# Tesseract_Pro-Mini.net
KiCad netlist of a schematic drawn in EAGLE
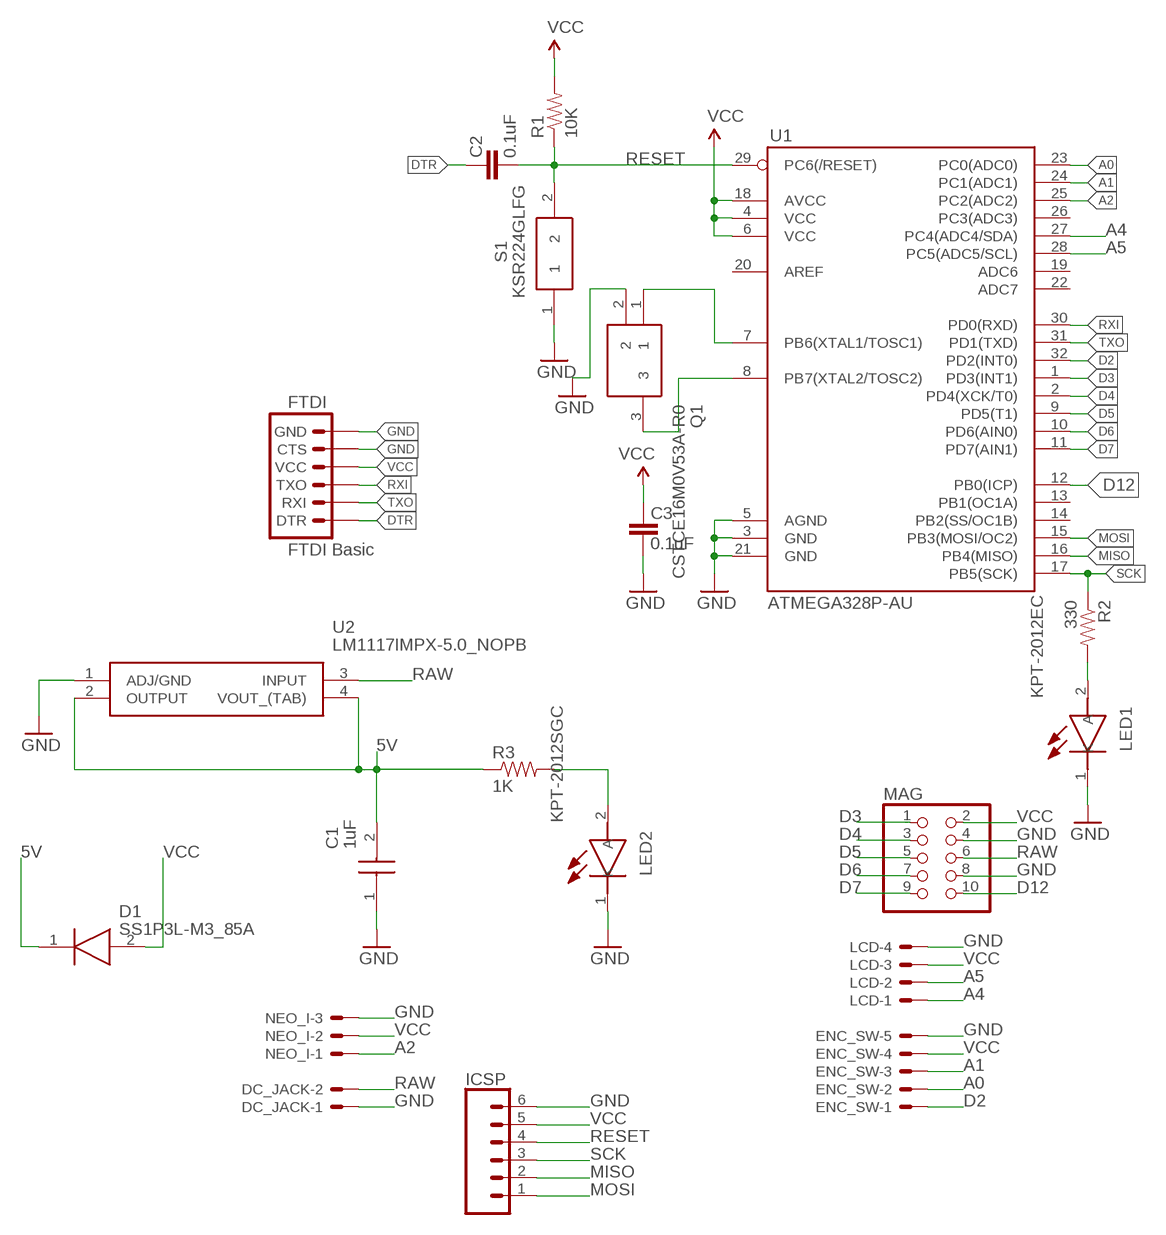
[diagram p0: schematic, sheet 1]

(export (version "E")
  (design (tool "Eeschema 10.0.6"))
  (components
    (comp (ref "C1")
      (value "1uF")
      (footprint "eagle-import:CAPC1608X90N")
      (fields
        (field (name "ARROW_PART_NUMBER") "GRM188R61E105KA12D")
        (field (name "RS_PART_NUMBER") "7235587P")
      )
      (libsource (lib "eagle-import") (part "GRM188R61E105KA12D"))
    )
    (comp (ref "C2")
      (value "0.1uF")
      (footprint "eagle-import:0603-CAP")
      (libsource (lib "eagle-import") (part "CAP0603-CAP"))
    )
    (comp (ref "C3")
      (value "0.1uF")
      (footprint "eagle-import:0603-CAP")
      (libsource (lib "eagle-import") (part "CAP0603-CAP"))
    )
    (comp (ref "D1")
      (value "SS1P3L-M3_85A")
      (footprint "eagle-import:SMP")
      (fields (field (name "ARROW_PART_NUMBER") "SS1P3L-M3/85A"))
      (libsource (lib "eagle-import") (part "SS1P3L-M3_85A"))
    )
    (comp (ref "DC_JACK")
      (value "JST-XH-02-PIN-LONG-PAD")
      (footprint "eagle-import:JST-XH-02-PACKAGE-LONG-PAD")
      (libsource (lib "eagle-import") (part "JST-XH-02-PIN-LONG-PAD"))
    )
    (comp (ref "ENC_SW")
      (value "JST-XH-05-PIN-LONG-PAD")
      (footprint "eagle-import:JST-XH-05-PACKAGE-LONG-PAD")
      (libsource (lib "eagle-import") (part "JST-XH-05-PIN-LONG-PAD"))
    )
    (comp (ref "FTDI")
      (value "FTDI Basic")
      (footprint "eagle-import:1X06")
      (libsource (lib "eagle-import") (part "ARDUINO_SERIAL_PROGRAMPTH"))
    )
    (comp (ref "ICSP")
      (value "CONN_06NO_SILK_NO_POP")
      (footprint "eagle-import:1X06_NO_SILK")
      (libsource (lib "eagle-import") (part "CONN_06NO_SILK_NO_POP"))
    )
    (comp (ref "LCD")
      (value "JST-XH-04-PIN-LONG-PAD")
      (footprint "eagle-import:JST-XH-04-PACKAGE-LONG-PAD")
      (libsource (lib "eagle-import") (part "JST-XH-04-PIN-LONG-PAD"))
    )
    (comp (ref "LED1")
      (value "KPT-2012EC")
      (footprint "eagle-import:LEDC2012X75N")
      (fields (field (name "RS_PART_NUMBER") "1651842"))
      (libsource (lib "eagle-import") (part "KPT-2012EC"))
    )
    (comp (ref "LED2")
      (value "KPT-2012SGC")
      (footprint "eagle-import:LEDM2012X120N")
      (fields (field (name "RS_PART_NUMBER") "8610188"))
      (libsource (lib "eagle-import") (part "KPT-2012SGC"))
    )
    (comp (ref "MAG")
      (value "PINHD-2X5")
      (footprint "eagle-import:2X05")
      (libsource (lib "eagle-import") (part "PINHD-2X5"))
    )
    (comp (ref "NEO_I")
      (value "JST-XH-03-PIN-LONG-PAD")
      (footprint "eagle-import:JST-XH-03-PACKAGE-LONG-PAD")
      (libsource (lib "eagle-import") (part "JST-XH-03-PIN-LONG-PAD"))
    )
    (comp (ref "Q1")
      (value "CSTCE16M0V53A-R0")
      (footprint "eagle-import:CSTCE-V_1")
      (fields (field (name "RS_PART_NUMBER") "1669524"))
      (libsource (lib "eagle-import") (part "CSTCE16M0V53A-R0"))
    )
    (comp (ref "R1")
      (value "10K")
      (footprint "eagle-import:0603-RES")
      (libsource (lib "eagle-import") (part "RESISTOR0603-RES"))
    )
    (comp (ref "R2")
      (value "330")
      (footprint "eagle-import:0603-RES")
      (libsource (lib "eagle-import") (part "RESISTOR0603-RES"))
    )
    (comp (ref "R3")
      (value "1K")
      (footprint "eagle-import:0603-RES")
      (libsource (lib "eagle-import") (part "RESISTOR0603-RES"))
    )
    (comp (ref "S1")
      (value "KSR224GLFG")
      (footprint "eagle-import:KSR211GLFS")
      (libsource (lib "eagle-import") (part "KSR224GLFG"))
    )
    (comp (ref "U1")
      (value "ATMEGA328P-AU")
      (footprint "eagle-import:TQFP32-08")
      (description "MICROCHIP - ATMEGA328P-AU. - MICROCONTROLLER MCU, 8 BIT, ATMEGA, 20MHZ, TQFP-32")
      (fields (field (name "MANUFACTURER") "Microchip") (field (name "RS_PART_NUMBER") "1310271"))
      (libsource (lib "eagle-import") (part "ATMEGA168"))
    )
    (comp (ref "U2")
      (value "LM1117IMPX-5.0_NOPB")
      (footprint "eagle-import:SOT230P700X180-4N")
      (fields (field (name "ARROW_PART_NUMBER") "LM1117IMPX-5.0/NOPB"))
      (libsource (lib "eagle-import") (part "LM1117IMPX-5.0_NOPB"))
    )
  )
  (nets
    (net (code "1") (name "/5V") (class "Default")
      (node (ref "C1") (pin "2") (pinfunction "2_2") (pintype "bidirectional"))
      (node (ref "D1") (pin "1") (pinfunction "A_1") (pintype "bidirectional"))
      (node (ref "R3") (pin "1") (pinfunction "1_1") (pintype "passive"))
      (node (ref "U2") (pin "2") (pinfunction "OUTPUT_2") (pintype "bidirectional"))
      (node (ref "U2") (pin "4") (pinfunction "VOUT_(TAB)_4") (pintype "bidirectional"))
    )
    (net (code "2") (name "/A4") (class "Default")
      (node (ref "LCD") (pin "1") (pinfunction "S_1") (pintype "passive"))
      (node (ref "U1") (pin "27") (pinfunction "PC4(ADC4/SDA)_27") (pintype "bidirectional"))
    )
    (net (code "3") (name "/A5") (class "Default")
      (node (ref "LCD") (pin "2") (pinfunction "S_2") (pintype "passive"))
      (node (ref "U1") (pin "28") (pinfunction "PC5(ADC5/SCL)_28") (pintype "bidirectional"))
    )
    (net (code "4") (name "/RAW") (class "Default")
      (node (ref "DC_JACK") (pin "2") (pinfunction "S_2") (pintype "passive"))
      (node (ref "MAG") (pin "6") (pinfunction "6_6") (pintype "passive"))
      (node (ref "U2") (pin "3") (pinfunction "INPUT_3") (pintype "bidirectional"))
    )
    (net (code "5") (name "/RESET") (class "Default")
      (node (ref "C2") (pin "1") (pinfunction "1_1") (pintype "passive"))
      (node (ref "ICSP") (pin "4") (pinfunction "4_4") (pintype "passive"))
      (node (ref "R1") (pin "1") (pinfunction "1_1") (pintype "passive"))
      (node (ref "S1") (pin "2") (pinfunction "2_2") (pintype "bidirectional"))
      (node (ref "U1") (pin "29") (pinfunction "PC6(/RESET)_29") (pintype "bidirectional"))
    )
    (net (code "6") (name "A0") (class "Default")
      (node (ref "ENC_SW") (pin "2") (pinfunction "S_2") (pintype "passive"))
      (node (ref "U1") (pin "23") (pinfunction "PC0(ADC0)_23") (pintype "bidirectional"))
    )
    (net (code "7") (name "A1") (class "Default")
      (node (ref "ENC_SW") (pin "3") (pinfunction "S_3") (pintype "passive"))
      (node (ref "U1") (pin "24") (pinfunction "PC1(ADC1)_24") (pintype "bidirectional"))
    )
    (net (code "8") (name "A2") (class "Default")
      (node (ref "NEO_I") (pin "1") (pinfunction "S_1") (pintype "passive"))
      (node (ref "U1") (pin "25") (pinfunction "PC2(ADC2)_25") (pintype "bidirectional"))
    )
    (net (code "9") (name "D2") (class "Default")
      (node (ref "ENC_SW") (pin "1") (pinfunction "S_1") (pintype "passive"))
      (node (ref "U1") (pin "32") (pinfunction "PD2(INT0)_32") (pintype "bidirectional"))
    )
    (net (code "10") (name "D3") (class "Default")
      (node (ref "MAG") (pin "1") (pinfunction "1_1") (pintype "passive"))
      (node (ref "U1") (pin "1") (pinfunction "PD3(INT1)_1") (pintype "bidirectional"))
    )
    (net (code "11") (name "D4") (class "Default")
      (node (ref "MAG") (pin "3") (pinfunction "3_3") (pintype "passive"))
      (node (ref "U1") (pin "2") (pinfunction "PD4(XCK/T0)_2") (pintype "bidirectional"))
    )
    (net (code "12") (name "D5") (class "Default")
      (node (ref "MAG") (pin "5") (pinfunction "5_5") (pintype "passive"))
      (node (ref "U1") (pin "9") (pinfunction "PD5(T1)_9") (pintype "bidirectional"))
    )
    (net (code "13") (name "D6") (class "Default")
      (node (ref "MAG") (pin "7") (pinfunction "7_7") (pintype "passive"))
      (node (ref "U1") (pin "10") (pinfunction "PD6(AIN0)_10") (pintype "bidirectional"))
    )
    (net (code "14") (name "D7") (class "Default")
      (node (ref "MAG") (pin "9") (pinfunction "9_9") (pintype "passive"))
      (node (ref "U1") (pin "11") (pinfunction "PD7(AIN1)_11") (pintype "bidirectional"))
    )
    (net (code "15") (name "D12") (class "Default")
      (node (ref "MAG") (pin "10") (pinfunction "10_10") (pintype "passive"))
      (node (ref "U1") (pin "12") (pinfunction "PB0(ICP)_12") (pintype "bidirectional"))
    )
    (net (code "16") (name "DTR") (class "Default")
      (node (ref "C2") (pin "2") (pinfunction "2_2") (pintype "passive"))
      (node (ref "FTDI") (pin "1") (pinfunction "DTR_1") (pintype "passive"))
    )
    (net (code "17") (name "GND") (class "Default")
      (node (ref "C1") (pin "1") (pinfunction "1_1") (pintype "bidirectional"))
      (node (ref "C3") (pin "1") (pinfunction "1_1") (pintype "passive"))
      (node (ref "DC_JACK") (pin "1") (pinfunction "S_1") (pintype "passive"))
      (node (ref "ENC_SW") (pin "5") (pinfunction "S_5") (pintype "passive"))
      (node (ref "FTDI") (pin "5") (pinfunction "CTS_5") (pintype "passive"))
      (node (ref "FTDI") (pin "6") (pinfunction "GND_6") (pintype "passive"))
      (node (ref "ICSP") (pin "6") (pinfunction "6_6") (pintype "passive"))
      (node (ref "LCD") (pin "4") (pinfunction "S_4") (pintype "passive"))
      (node (ref "LED1") (pin "1") (pinfunction "K_1") (pintype "bidirectional"))
      (node (ref "LED2") (pin "1") (pinfunction "K_1") (pintype "power_in"))
      (node (ref "MAG") (pin "4") (pinfunction "4_4") (pintype "passive"))
      (node (ref "MAG") (pin "8") (pinfunction "8_8") (pintype "passive"))
      (node (ref "NEO_I") (pin "3") (pinfunction "S_3") (pintype "passive"))
      (node (ref "Q1") (pin "2") (pinfunction "2_2") (pintype "bidirectional"))
      (node (ref "S1") (pin "1") (pinfunction "1_1") (pintype "bidirectional"))
      (node (ref "U1") (pin "21") (pinfunction "GND_21") (pintype "bidirectional"))
      (node (ref "U1") (pin "3") (pinfunction "GND_3") (pintype "bidirectional"))
      (node (ref "U1") (pin "5") (pinfunction "AGND_5") (pintype "bidirectional"))
      (node (ref "U2") (pin "1") (pinfunction "ADJ/GND_1") (pintype "bidirectional"))
    )
    (net (code "18") (name "MISO") (class "Default")
      (node (ref "ICSP") (pin "2") (pinfunction "2_2") (pintype "passive"))
      (node (ref "U1") (pin "16") (pinfunction "PB4(MISO)_16") (pintype "bidirectional"))
    )
    (net (code "19") (name "MOSI") (class "Default")
      (node (ref "ICSP") (pin "1") (pinfunction "1_1") (pintype "passive"))
      (node (ref "U1") (pin "15") (pinfunction "PB3(MOSI/OC2)_15") (pintype "bidirectional"))
    )
    (net (code "20") (name "Net-(LED1-A)") (class "Default")
      (node (ref "LED1") (pin "2") (pinfunction "A_2") (pintype "bidirectional"))
      (node (ref "R2") (pin "2") (pinfunction "2_2") (pintype "passive"))
    )
    (net (code "21") (name "Net-(LED2-A)") (class "Default")
      (node (ref "LED2") (pin "2") (pinfunction "A_2") (pintype "power_in"))
      (node (ref "R3") (pin "2") (pinfunction "2_2") (pintype "passive"))
    )
    (net (code "22") (name "Net-(U1-PB6(XTAL1{slash}TOSC1))") (class "Default")
      (node (ref "Q1") (pin "1") (pinfunction "1_1") (pintype "bidirectional"))
      (node (ref "U1") (pin "7") (pinfunction "PB6(XTAL1/TOSC1)_7") (pintype "bidirectional"))
    )
    (net (code "23") (name "Net-(U1-PB7(XTAL2{slash}TOSC2))") (class "Default")
      (node (ref "Q1") (pin "3") (pinfunction "3_3") (pintype "bidirectional"))
      (node (ref "U1") (pin "8") (pinfunction "PB7(XTAL2/TOSC2)_8") (pintype "bidirectional"))
    )
    (net (code "24") (name "RXI") (class "Default")
      (node (ref "FTDI") (pin "3") (pinfunction "TXO_3") (pintype "passive"))
      (node (ref "U1") (pin "30") (pinfunction "PD0(RXD)_30") (pintype "bidirectional"))
    )
    (net (code "25") (name "SCK") (class "Default")
      (node (ref "ICSP") (pin "3") (pinfunction "3_3") (pintype "passive"))
      (node (ref "R2") (pin "1") (pinfunction "1_1") (pintype "passive"))
      (node (ref "U1") (pin "17") (pinfunction "PB5(SCK)_17") (pintype "bidirectional"))
    )
    (net (code "26") (name "TXO") (class "Default")
      (node (ref "FTDI") (pin "2") (pinfunction "RXI_2") (pintype "passive"))
      (node (ref "U1") (pin "31") (pinfunction "PD1(TXD)_31") (pintype "bidirectional"))
    )
    (net (code "27") (name "VCC") (class "Default")
      (node (ref "C3") (pin "2") (pinfunction "2_2") (pintype "passive"))
      (node (ref "D1") (pin "2") (pinfunction "K_2") (pintype "bidirectional"))
      (node (ref "ENC_SW") (pin "4") (pinfunction "S_4") (pintype "passive"))
      (node (ref "FTDI") (pin "4") (pinfunction "VCC_4") (pintype "passive"))
      (node (ref "ICSP") (pin "5") (pinfunction "5_5") (pintype "passive"))
      (node (ref "LCD") (pin "3") (pinfunction "S_3") (pintype "passive"))
      (node (ref "MAG") (pin "2") (pinfunction "2_2") (pintype "passive"))
      (node (ref "NEO_I") (pin "2") (pinfunction "S_2") (pintype "passive"))
      (node (ref "R1") (pin "2") (pinfunction "2_2") (pintype "passive"))
      (node (ref "U1") (pin "18") (pinfunction "AVCC_18") (pintype "bidirectional"))
      (node (ref "U1") (pin "4") (pinfunction "VCC_4") (pintype "bidirectional"))
      (node (ref "U1") (pin "6") (pinfunction "VCC_6") (pintype "bidirectional"))
    )
    (net (code "28") (name "unconnected-(U1-ADC6-Pad19)") (class "Default")
      (node (ref "U1") (pin "19") (pinfunction "ADC6_19") (pintype "bidirectional"))
    )
    (net (code "29") (name "unconnected-(U1-ADC7-Pad22)") (class "Default")
      (node (ref "U1") (pin "22") (pinfunction "ADC7_22") (pintype "bidirectional"))
    )
    (net (code "30") (name "unconnected-(U1-AREF-Pad20)") (class "Default")
      (node (ref "U1") (pin "20") (pinfunction "AREF_20") (pintype "bidirectional"))
    )
    (net (code "31") (name "unconnected-(U1-PB1(OC1A)-Pad13)") (class "Default")
      (node (ref "U1") (pin "13") (pinfunction "PB1(OC1A)_13") (pintype "bidirectional"))
    )
    (net (code "32") (name "unconnected-(U1-PB2(SS{slash}OC1B)-Pad14)") (class "Default")
      (node (ref "U1") (pin "14") (pinfunction "PB2(SS/OC1B)_14") (pintype "bidirectional"))
    )
    (net (code "33") (name "unconnected-(U1-PC3(ADC3)-Pad26)") (class "Default")
      (node (ref "U1") (pin "26") (pinfunction "PC3(ADC3)_26") (pintype "bidirectional"))
    )
  )
)
